# Main.net
KiCad netlist of a schematic drawn in Altium Designer
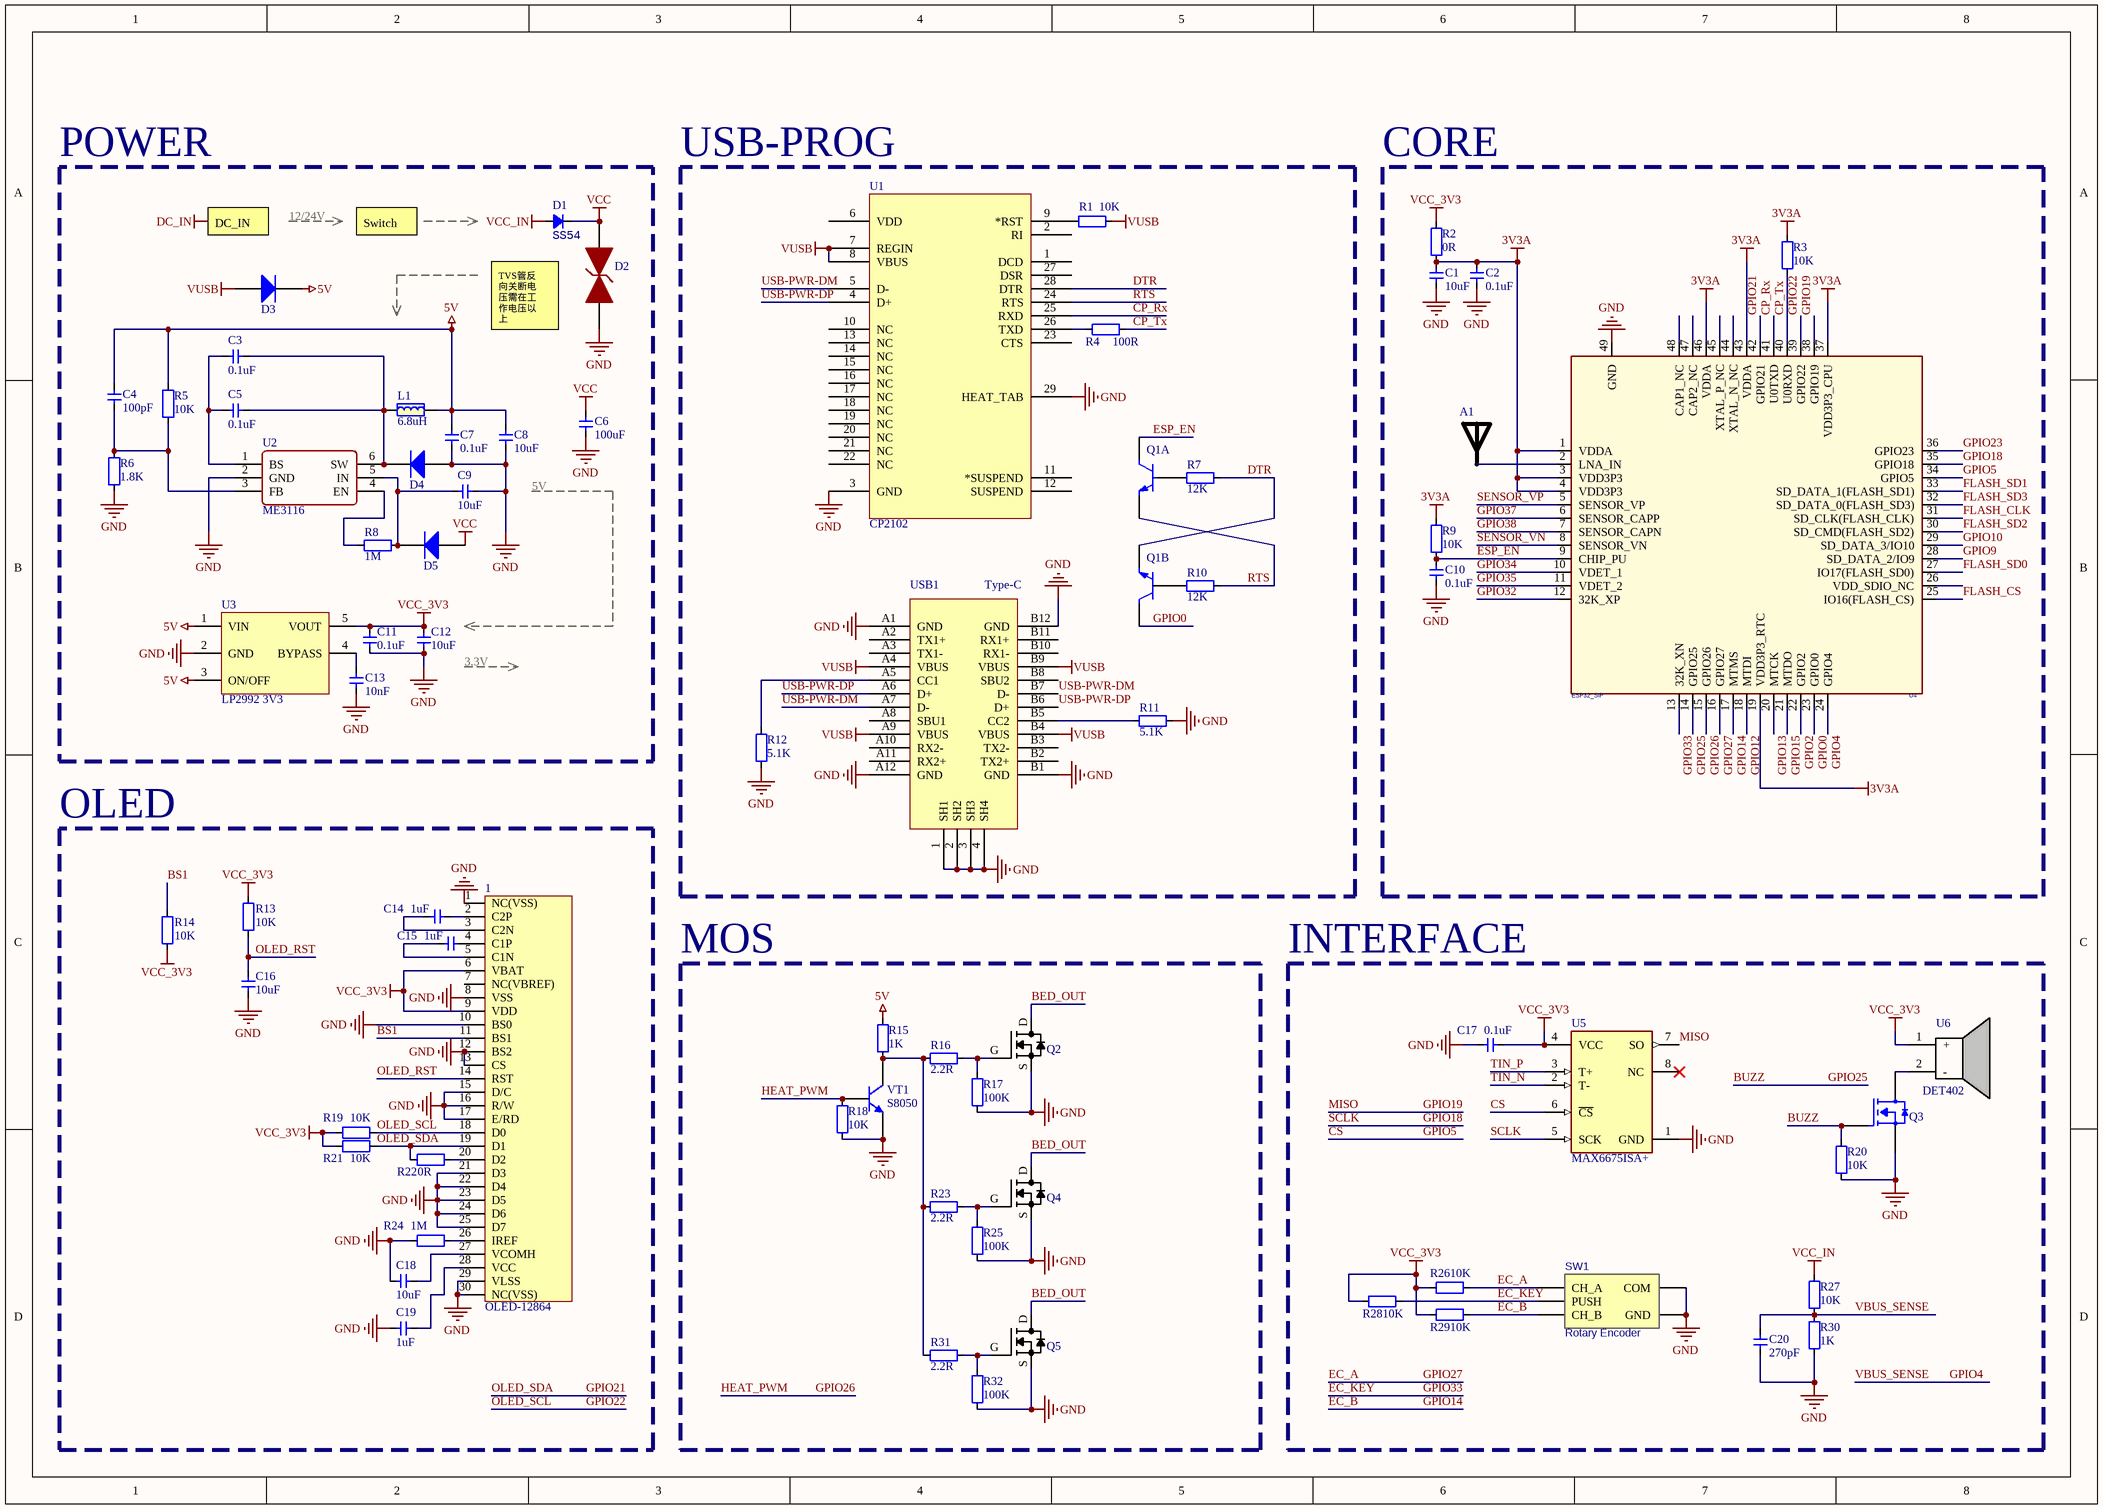
[diagram p0: Main.SchDoc]

(export (version "E")
  (design (tool "Eeschema 10.0.6"))
  (components
    (comp (ref "1")
      (value "OLED-12864")
      (footprint "OLED-12864-1.3-TOP")
      (description "显示屏")
      (libsource (lib "MyPcbLib") (part "OLED-12864"))
    )
    (comp (ref "A1")
      (value "RAINSUN")
      (footprint "ANT-Rainsun-AN5120")
      (libsource (lib "MyPcbLib") (part "ANT-Rainsun-AP5120"))
    )
    (comp (ref "C1")
      (value "10uF")
      (footprint "CAP_0402")
      (description "Capacitor")
      (libsource (lib "MyPcbLib") (part "电容-0402"))
    )
    (comp (ref "C2")
      (value "0.1uF")
      (footprint "CAP_0402")
      (description "Capacitor")
      (libsource (lib "MyPcbLib") (part "电容-0402"))
    )
    (comp (ref "C3")
      (value "0.1uF")
      (footprint "CAP_0402")
      (description "Capacitor")
      (libsource (lib "MyPcbLib") (part "电容-0402"))
    )
    (comp (ref "C4")
      (value "100pF")
      (footprint "CAP_0402")
      (description "Capacitor")
      (libsource (lib "MyPcbLib") (part "电容-0402"))
    )
    (comp (ref "C5")
      (value "0.1uF")
      (footprint "CAP_0402")
      (description "Capacitor")
      (libsource (lib "MyPcbLib") (part "电容-0402"))
    )
    (comp (ref "C6")
      (value "100uF")
      (footprint "1206-CAP")
      (description "Capacitor")
      (libsource (lib "MyPcbLib") (part "电容-1206"))
    )
    (comp (ref "C7")
      (value "0.1uF")
      (footprint "CAP_0402")
      (description "Capacitor")
      (libsource (lib "MyPcbLib") (part "电容-0402"))
    )
    (comp (ref "C8")
      (value "10uF")
      (footprint "CAP_0402")
      (description "Capacitor")
      (libsource (lib "MyPcbLib") (part "电容-0402"))
    )
    (comp (ref "C9")
      (value "10uF")
      (footprint "CAP_0402")
      (description "Capacitor")
      (libsource (lib "MyPcbLib") (part "电容-0402"))
    )
    (comp (ref "C10")
      (value "0.1uF")
      (footprint "CAP_0402")
      (description "Capacitor")
      (libsource (lib "MyPcbLib") (part "电容-0402"))
    )
    (comp (ref "C11")
      (value "0.1uF")
      (footprint "CAP_0402")
      (description "Capacitor")
      (libsource (lib "MyPcbLib") (part "电容-0402"))
    )
    (comp (ref "C12")
      (value "10uF")
      (footprint "CAP_0402")
      (description "Capacitor")
      (libsource (lib "MyPcbLib") (part "电容-0402"))
    )
    (comp (ref "C13")
      (value "10nF")
      (footprint "CAP_0402")
      (description "Capacitor")
      (libsource (lib "MyPcbLib") (part "电容-0402"))
    )
    (comp (ref "C14")
      (value "1uF")
      (footprint "CAP_0402")
      (description "Capacitor")
      (libsource (lib "MyPcbLib") (part "电容-0402"))
    )
    (comp (ref "C15")
      (value "1uF")
      (footprint "CAP_0402")
      (description "Capacitor")
      (libsource (lib "MyPcbLib") (part "电容-0402"))
    )
    (comp (ref "C16")
      (value "10uF")
      (footprint "CAP_0402")
      (description "Capacitor")
      (libsource (lib "MyPcbLib") (part "电容-0402"))
    )
    (comp (ref "C17")
      (value "0.1uF")
      (footprint "CAP_0402")
      (description "Capacitor")
      (libsource (lib "MyPcbLib") (part "电容-0402"))
    )
    (comp (ref "C18")
      (value "10uF")
      (footprint "CAP_0402")
      (description "Capacitor")
      (libsource (lib "MyPcbLib") (part "电容-0402"))
    )
    (comp (ref "C19")
      (value "1uF")
      (footprint "CAP_0402")
      (description "Capacitor")
      (libsource (lib "MyPcbLib") (part "电容-0402"))
    )
    (comp (ref "C20")
      (value "270pF")
      (footprint "CAP_0402")
      (description "Capacitor")
      (libsource (lib "MyPcbLib") (part "电容-0402"))
    )
    (comp (ref "D1")
      (value "SS54")
      (footprint "DO-214AC")
      (description "Diode")
      (libsource (lib "KitSprout") (part "Diode_SMA"))
    )
    (comp (ref "D2")
      (value "SMBJ28CA")
      (footprint "SMBJ-CA_MFG")
      (libsource (lib "MyPcbLib") (part "SMBJ28CA"))
    )
    (comp (ref "D3")
      (value "二极管-5819W")
      (footprint "SOD-323")
      (description "40V")
      (libsource (lib "MyPcbLib") (part "二极管-5819W"))
    )
    (comp (ref "D4")
      (value "二极管-5819W")
      (footprint "SOD-323")
      (description "40V")
      (libsource (lib "MyPcbLib") (part "二极管-5819W"))
    )
    (comp (ref "D5")
      (value "二极管-5819W")
      (footprint "SOD-323")
      (description "40V")
      (libsource (lib "MyPcbLib") (part "二极管-5819W"))
    )
    (comp (ref "L1") (value "6.8uH") (footprint "IND-201612") (libsource (lib "MyPcbLib") (part "电感-201612")))
    (comp (ref "Q1")
      (value "BC847BVC-7")
      (footprint "SOT563-6")
      (libsource (lib "MyPcbLib") (part "BC847BVC-7"))
    )
    (comp (ref "Q2")
      (value "NTMFS5C628NLT")
      (footprint "SO8FL")
      (description "MOSFET N-CH 60V SO8FL")
      (fields
        (field (name "MANUFACTURER") "ON Semiconductor")
        (field (name "MANUFACTURER PART NUMBER") "NTMFS5C628NLT1G")
      )
      (libsource (lib "MyPcbLib") (part "NTMFS5C628NLT"))
    )
    (comp (ref "Q3")
      (value "AO3400A")
      (footprint "SOT23-3")
      (description "N-MOS")
      (libsource (lib "MyPcbLib") (part "AO3400A"))
    )
    (comp (ref "Q4")
      (value "NTMFS5C628NLT")
      (footprint "SO8FL")
      (description "MOSFET N-CH 60V SO8FL")
      (fields
        (field (name "MANUFACTURER") "ON Semiconductor")
        (field (name "MANUFACTURER PART NUMBER") "NTMFS5C628NLT1G")
      )
      (libsource (lib "MyPcbLib") (part "NTMFS5C628NLT"))
    )
    (comp (ref "Q5")
      (value "NTMFS5C628NLT")
      (footprint "SO8FL")
      (description "MOSFET N-CH 60V SO8FL")
      (fields
        (field (name "MANUFACTURER") "ON Semiconductor")
        (field (name "MANUFACTURER PART NUMBER") "NTMFS5C628NLT1G")
      )
      (libsource (lib "MyPcbLib") (part "NTMFS5C628NLT"))
    )
    (comp (ref "R1")
      (value "10K")
      (footprint "RES_0402")
      (description "Resistor")
      (libsource (lib "") (part "电阻-0402_1"))
    )
    (comp (ref "R2")
      (value "0R")
      (footprint "RES_0402")
      (description "Resistor")
      (libsource (lib "") (part "电阻-0402_2"))
    )
    (comp (ref "R3")
      (value "10K")
      (footprint "RES_0402")
      (description "Resistor")
      (libsource (lib "") (part "电阻-0402_3"))
    )
    (comp (ref "R4")
      (value "100R")
      (footprint "RES_0402")
      (description "Resistor")
      (libsource (lib "") (part "电阻-0402_1"))
    )
    (comp (ref "R5")
      (value "10K")
      (footprint "RES_0402")
      (description "Resistor")
      (libsource (lib "") (part "电阻-0402_3"))
    )
    (comp (ref "R6")
      (value "1.8K")
      (footprint "RES_0402")
      (description "Resistor")
      (libsource (lib "") (part "电阻-0402_3"))
    )
    (comp (ref "R7")
      (value "12K")
      (footprint "RES_0402")
      (description "Resistor")
      (libsource (lib "") (part "电阻-0402_1"))
    )
    (comp (ref "R8")
      (value "1M")
      (footprint "RES_0402")
      (description "Resistor")
      (libsource (lib "") (part "电阻-0402_1"))
    )
    (comp (ref "R9")
      (value "10K")
      (footprint "RES_0402")
      (description "Resistor")
      (libsource (lib "") (part "电阻-0402_2"))
    )
    (comp (ref "R10")
      (value "12K")
      (footprint "RES_0402")
      (description "Resistor")
      (libsource (lib "") (part "电阻-0402_1"))
    )
    (comp (ref "R11")
      (value "5.1K")
      (footprint "RES_0402")
      (description "Resistor")
      (libsource (lib "") (part "电阻-0402_1"))
    )
    (comp (ref "R12")
      (value "5.1K")
      (footprint "RES_0402")
      (description "Resistor")
      (libsource (lib "") (part "电阻-0402_2"))
    )
    (comp (ref "R13")
      (value "10K")
      (footprint "RES_0402")
      (description "Resistor")
      (libsource (lib "") (part "电阻-0402_3"))
    )
    (comp (ref "R14")
      (value "10K")
      (footprint "RES_0402")
      (description "Resistor")
      (libsource (lib "") (part "电阻-0402_3"))
    )
    (comp (ref "R15")
      (value "1K")
      (footprint "RES_0402")
      (description "Resistor")
      (libsource (lib "") (part "电阻-0402_3"))
    )
    (comp (ref "R16")
      (value "2.2R")
      (footprint "RES_0402")
      (description "Resistor")
      (libsource (lib "") (part "电阻-0402_1"))
    )
    (comp (ref "R17")
      (value "100K")
      (footprint "RES_0402")
      (description "Resistor")
      (libsource (lib "") (part "电阻-0402_2"))
    )
    (comp (ref "R18")
      (value "10K")
      (footprint "RES_0402")
      (description "Resistor")
      (libsource (lib "") (part "电阻-0402_2"))
    )
    (comp (ref "R19")
      (value "10K")
      (footprint "RES_0402")
      (description "Resistor")
      (libsource (lib "MyPcbLib") (part "电阻-0402"))
    )
    (comp (ref "R20")
      (value "10K")
      (footprint "RES_0402")
      (description "Resistor")
      (libsource (lib "") (part "电阻-0402_3"))
    )
    (comp (ref "R21")
      (value "10K")
      (footprint "RES_0402")
      (description "Resistor")
      (libsource (lib "MyPcbLib") (part "电阻-0402"))
    )
    (comp (ref "R22")
      (value "0R")
      (footprint "RES_0402")
      (description "Resistor")
      (libsource (lib "") (part "电阻-0402_1"))
    )
    (comp (ref "R23")
      (value "2.2R")
      (footprint "RES_0402")
      (description "Resistor")
      (libsource (lib "") (part "电阻-0402_1"))
    )
    (comp (ref "R24")
      (value "1M")
      (footprint "RES_0402")
      (description "Resistor")
      (libsource (lib "MyPcbLib") (part "电阻-0402"))
    )
    (comp (ref "R25")
      (value "100K")
      (footprint "RES_0402")
      (description "Resistor")
      (libsource (lib "") (part "电阻-0402_2"))
    )
    (comp (ref "R26")
      (value "10K")
      (footprint "RES_0402")
      (description "Resistor")
      (libsource (lib "") (part "电阻-0402_1"))
    )
    (comp (ref "R27")
      (value "10K")
      (footprint "RES_0402")
      (description "Resistor")
      (libsource (lib "") (part "电阻-0402_2"))
    )
    (comp (ref "R28")
      (value "10K")
      (footprint "RES_0402")
      (description "Resistor")
      (libsource (lib "") (part "电阻-0402_1"))
    )
    (comp (ref "R29")
      (value "10K")
      (footprint "RES_0402")
      (description "Resistor")
      (libsource (lib "") (part "电阻-0402_1"))
    )
    (comp (ref "R30")
      (value "1K")
      (footprint "RES_0402")
      (description "Resistor")
      (libsource (lib "") (part "电阻-0402_2"))
    )
    (comp (ref "R31")
      (value "2.2R")
      (footprint "RES_0402")
      (description "Resistor")
      (libsource (lib "") (part "电阻-0402_1"))
    )
    (comp (ref "R32")
      (value "100K")
      (footprint "RES_0402")
      (description "Resistor")
      (libsource (lib "") (part "电阻-0402_2"))
    )
    (comp (ref "SW1")
      (value "Rotary Encoder")
      (footprint "SIQ-02FVS3")
      (fields
        (field (name "BOM_SUPPLIER PART") "C1322543")
        (field (name "BOM_MANUFACTURER PART") "EC11E1534443")
        (field (name "CONTRIBUTOR") "LCSC")
      )
      (libsource (lib "MyPcbLib") (part "Rotary Encoder"))
    )
    (comp (ref "U1")
      (value "CP2102")
      (footprint "QFN-28")
      (description "USB转TTL")
      (libsource (lib "mLib") (part "CP2102"))
    )
    (comp (ref "U2")
      (value "ME3116")
      (footprint "SOT23-6")
      (description "DC-DC")
      (libsource (lib "MyPcbLib") (part "ME3116"))
    )
    (comp (ref "U3")
      (value "LP2992 3V3")
      (footprint "SOT23-5")
      (description "LDO")
      (libsource (lib "mLib") (part "LP2992"))
    )
    (comp (ref "U4")
      (value "ESP32_SIP")
      (footprint "QFN-48_7X7")
      (libsource (lib "mLib") (part "ESP32-PICO"))
    )
    (comp (ref "U5")
      (value "MAX6675ISA")
      (footprint "SO-8")
      (description "IC THERMOCOUP TO DGTL 8-SOIC")
      (fields
        (field (name "MANUFACTURER") "Maxim Electronics")
        (field (name "OCTOPART PART NUMBER") "33bcfab92ad8ec7b")
        (field (name "PART NUMBER") "MAX6675ISA+")
      )
      (libsource (lib "MyPcbLib") (part "MAX6675ISA"))
    )
    (comp (ref "U6") (value "DET402") (footprint "DET402") (libsource (lib "MyPcbLib") (part "DET402")))
    (comp (ref "USB1")
      (value "Type-C")
      (footprint "Type-C-TOP")
      (libsource (lib "MyPcbLib") (part "USB-Type-C-TOP"))
    )
    (comp (ref "VT1")
      (value "S8050")
      (footprint "SMT_TRIODE_NPN")
      (description "Surface mount NPN transistor, package SOT-23")
      (libsource (lib "MyPcbLib") (part "SMT_TRIODE_NPN"))
    )
  )
  (nets
    (net (code "1") (name "/BED_OUT") (class "Default")
      (node (ref "Q2") (pin "D") (pinfunction "D_D") (pintype "passive"))
      (node (ref "Q4") (pin "D") (pinfunction "D_D") (pintype "passive"))
      (node (ref "Q5") (pin "D") (pinfunction "D_D") (pintype "passive"))
    )
    (net (code "2") (name "/BS1") (class "Default")
      (node (ref "1") (pin "11") (pinfunction "BS1_11") (pintype "passive"))
      (node (ref "R14") (pin "2") (pinfunction "2_2") (pintype "passive"))
    )
    (net (code "3") (name "/BUZZ") (class "Default")
      (node (ref "Q3") (pin "1") (pinfunction "G_1") (pintype "passive"))
      (node (ref "R20") (pin "2") (pinfunction "2_2") (pintype "passive"))
      (node (ref "U4") (pin "14") (pinfunction "GPIO25_14") (pintype "passive"))
    )
    (net (code "4") (name "/CP_Rx") (class "Default")
      (node (ref "U1") (pin "25") (pinfunction "RXD_25") (pintype "passive"))
      (node (ref "U4") (pin "41") (pinfunction "U0TXD_41") (pintype "power_in"))
    )
    (net (code "5") (name "/CP_Tx") (class "Default")
      (node (ref "R3") (pin "1") (pinfunction "1_1") (pintype "passive"))
      (node (ref "R4") (pin "1") (pinfunction "1_1") (pintype "passive"))
      (node (ref "U4") (pin "40") (pinfunction "U0RXD_40") (pintype "power_in"))
    )
    (net (code "6") (name "/CS") (class "Default")
      (node (ref "U4") (pin "34") (pinfunction "GPIO5_34") (pintype "passive"))
      (node (ref "U5") (pin "6") (pinfunction "~{CS}_6") (pintype "input"))
    )
    (net (code "7") (name "/DTR") (class "Default")
      (node (ref "Q1") (pin "4") (pinfunction "E2_4") (pintype "passive"))
      (node (ref "R7") (pin "1") (pinfunction "1_1") (pintype "passive"))
      (node (ref "U1") (pin "28") (pinfunction "DTR_28") (pintype "passive"))
    )
    (net (code "8") (name "/EC_A") (class "Default")
      (node (ref "R26") (pin "1") (pinfunction "1_1") (pintype "passive"))
      (node (ref "SW1") (pin "1") (pinfunction "CH_A_1") (pintype "passive"))
      (node (ref "U4") (pin "16") (pinfunction "GPIO27_16") (pintype "passive"))
    )
    (net (code "9") (name "/EC_B") (class "Default")
      (node (ref "R29") (pin "1") (pinfunction "1_1") (pintype "passive"))
      (node (ref "SW1") (pin "4") (pinfunction "CH_B_4") (pintype "passive"))
      (node (ref "U4") (pin "17") (pinfunction "MTMS_17") (pintype "passive"))
    )
    (net (code "10") (name "/EC_KEY") (class "Default")
      (node (ref "R28") (pin "1") (pinfunction "1_1") (pintype "passive"))
      (node (ref "SW1") (pin "2") (pinfunction "PUSH_2") (pintype "passive"))
      (node (ref "U4") (pin "13") (pinfunction "32K_XN_13") (pintype "passive"))
    )
    (net (code "11") (name "/ESP_EN") (class "Default")
      (node (ref "C10") (pin "1") (pinfunction "1_1") (pintype "passive"))
      (node (ref "Q1") (pin "6") (pinfunction "C1_6") (pintype "passive"))
      (node (ref "R9") (pin "2") (pinfunction "2_2") (pintype "passive"))
      (node (ref "U4") (pin "9") (pinfunction "CHIP_PU_9") (pintype "passive"))
    )
    (net (code "12") (name "/FLASH_CLK") (class "Default")
      (node (ref "U4") (pin "31") (pinfunction "SD_CLK(FLASH_CLK)_31") (pintype "passive"))
    )
    (net (code "13") (name "/FLASH_CS") (class "Default")
      (node (ref "U4") (pin "25") (pinfunction "IO16(FLASH_CS)_25") (pintype "passive"))
    )
    (net (code "14") (name "/FLASH_SD0") (class "Default")
      (node (ref "U4") (pin "27") (pinfunction "IO17(FLASH_SD0)_27") (pintype "passive"))
    )
    (net (code "15") (name "/FLASH_SD1") (class "Default")
      (node (ref "U4") (pin "33") (pinfunction "SD_DATA_1(FLASH_SD1)_33") (pintype "passive"))
    )
    (net (code "16") (name "/FLASH_SD2") (class "Default")
      (node (ref "U4") (pin "30") (pinfunction "SD_CMD(FLASH_SD2)_30") (pintype "passive"))
    )
    (net (code "17") (name "/FLASH_SD3") (class "Default")
      (node (ref "U4") (pin "32") (pinfunction "SD_DATA_0(FLASH_SD3)_32") (pintype "passive"))
    )
    (net (code "18") (name "/GPIO0") (class "Default")
      (node (ref "Q1") (pin "3") (pinfunction "C2_3") (pintype "passive"))
      (node (ref "U4") (pin "23") (pinfunction "GPIO0_23") (pintype "passive"))
    )
    (net (code "19") (name "/GPIO2") (class "Default")
      (node (ref "U4") (pin "22") (pinfunction "GPIO2_22") (pintype "passive"))
    )
    (net (code "20") (name "/GPIO4") (class "Default")
      (node (ref "C20") (pin "2") (pinfunction "2_2") (pintype "passive"))
      (node (ref "R27") (pin "2") (pinfunction "2_2") (pintype "passive"))
      (node (ref "R30") (pin "1") (pinfunction "1_1") (pintype "passive"))
      (node (ref "U4") (pin "24") (pinfunction "GPIO4_24") (pintype "passive"))
    )
    (net (code "21") (name "/GPIO9") (class "Default")
      (node (ref "U4") (pin "28") (pinfunction "SD_DATA_2/IO9_28") (pintype "passive"))
    )
    (net (code "22") (name "/GPIO10") (class "Default")
      (node (ref "U4") (pin "29") (pinfunction "SD_DATA_3/IO10_29") (pintype "passive"))
    )
    (net (code "23") (name "/GPIO12") (class "Default")
      (node (ref "U4") (pin "18") (pinfunction "MTDI_18") (pintype "passive"))
    )
    (net (code "24") (name "/GPIO13") (class "Default")
      (node (ref "U4") (pin "20") (pinfunction "MTCK_20") (pintype "passive"))
    )
    (net (code "25") (name "/GPIO15") (class "Default")
      (node (ref "U4") (pin "21") (pinfunction "MTDO_21") (pintype "passive"))
    )
    (net (code "26") (name "/GPIO18") (class "Default")
      (node (ref "U4") (pin "35") (pinfunction "GPIO18_35") (pintype "passive"))
      (node (ref "U5") (pin "5") (pinfunction "SCK_5") (pintype "input"))
    )
    (net (code "27") (name "/GPIO19") (class "Default")
      (node (ref "U4") (pin "38") (pinfunction "GPIO19_38") (pintype "passive"))
      (node (ref "U5") (pin "7") (pinfunction "SO_7") (pintype "output"))
    )
    (net (code "28") (name "/GPIO21") (class "Default")
      (node (ref "1") (pin "19") (pinfunction "D1_19") (pintype "passive"))
      (node (ref "R21") (pin "2") (pinfunction "2_2") (pintype "passive"))
      (node (ref "R22") (pin "2") (pinfunction "2_2") (pintype "passive"))
      (node (ref "U4") (pin "42") (pinfunction "GPIO21_42") (pintype "passive"))
    )
    (net (code "29") (name "/GPIO22") (class "Default")
      (node (ref "1") (pin "18") (pinfunction "D0_18") (pintype "passive"))
      (node (ref "R19") (pin "2") (pinfunction "2_2") (pintype "passive"))
      (node (ref "U4") (pin "39") (pinfunction "GPIO22_39") (pintype "passive"))
    )
    (net (code "30") (name "/GPIO23") (class "Default")
      (node (ref "U4") (pin "36") (pinfunction "GPIO23_36") (pintype "passive"))
    )
    (net (code "31") (name "/GPIO26") (class "Default")
      (node (ref "R18") (pin "1") (pinfunction "1_1") (pintype "passive"))
      (node (ref "U4") (pin "15") (pinfunction "GPIO26_15") (pintype "passive"))
      (node (ref "VT1") (pin "1") (pinfunction "B_1") (pintype "passive"))
    )
    (net (code "32") (name "/GPIO32") (class "Default")
      (node (ref "U4") (pin "12") (pinfunction "32K_XP_12") (pintype "passive"))
    )
    (net (code "33") (name "/GPIO34") (class "Default")
      (node (ref "U4") (pin "10") (pinfunction "VDET_1_10") (pintype "passive"))
    )
    (net (code "34") (name "/GPIO35") (class "Default")
      (node (ref "U4") (pin "11") (pinfunction "VDET_2_11") (pintype "passive"))
    )
    (net (code "35") (name "/GPIO37") (class "Default")
      (node (ref "U4") (pin "6") (pinfunction "SENSOR_CAPP_6") (pintype "passive"))
    )
    (net (code "36") (name "/GPIO38") (class "Default")
      (node (ref "U4") (pin "7") (pinfunction "SENSOR_CAPN_7") (pintype "passive"))
    )
    (net (code "37") (name "/OLED_RST") (class "Default")
      (node (ref "1") (pin "14") (pinfunction "RST_14") (pintype "passive"))
      (node (ref "C16") (pin "2") (pinfunction "2_2") (pintype "passive"))
      (node (ref "R13") (pin "1") (pinfunction "1_1") (pintype "passive"))
    )
    (net (code "38") (name "/RTS") (class "Default")
      (node (ref "Q1") (pin "1") (pinfunction "E1_1") (pintype "passive"))
      (node (ref "R10") (pin "1") (pinfunction "1_1") (pintype "passive"))
      (node (ref "U1") (pin "24") (pinfunction "RTS_24") (pintype "passive"))
    )
    (net (code "39") (name "/SENSOR_VN") (class "Default")
      (node (ref "U4") (pin "8") (pinfunction "SENSOR_VN_8") (pintype "passive"))
    )
    (net (code "40") (name "/SENSOR_VP") (class "Default")
      (node (ref "U4") (pin "5") (pinfunction "SENSOR_VP_5") (pintype "passive"))
    )
    (net (code "41") (name "/TIN_N") (class "Default")
      (node (ref "U5") (pin "2") (pinfunction "T-_2") (pintype "input"))
    )
    (net (code "42") (name "/TIN_P") (class "Default")
      (node (ref "U5") (pin "3") (pinfunction "T+_3") (pintype "input"))
    )
    (net (code "43") (name "/USB-PWR-DM") (class "Default")
      (node (ref "U1") (pin "5") (pinfunction "D-_5") (pintype "passive"))
      (node (ref "USB1") (pin "A7") (pinfunction "D-_A7") (pintype "passive"))
      (node (ref "USB1") (pin "B7") (pinfunction "D-_B7") (pintype "passive"))
    )
    (net (code "44") (name "/USB-PWR-DP") (class "Default")
      (node (ref "U1") (pin "4") (pinfunction "D+_4") (pintype "passive"))
      (node (ref "USB1") (pin "A6") (pinfunction "D+_A6") (pintype "passive"))
      (node (ref "USB1") (pin "B6") (pinfunction "D+_B6") (pintype "passive"))
    )
    (net (code "45") (name "3V3A") (class "Default")
      (node (ref "C1") (pin "2") (pinfunction "2_2") (pintype "passive"))
      (node (ref "C2") (pin "2") (pinfunction "2_2") (pintype "passive"))
      (node (ref "R2") (pin "2") (pinfunction "2_2") (pintype "passive"))
      (node (ref "R3") (pin "2") (pinfunction "2_2") (pintype "passive"))
      (node (ref "R9") (pin "1") (pinfunction "1_1") (pintype "passive"))
      (node (ref "U4") (pin "1") (pinfunction "VDDA_1") (pintype "power_in"))
      (node (ref "U4") (pin "19") (pinfunction "VDD3P3_RTC_19") (pintype "power_in"))
      (node (ref "U4") (pin "3") (pinfunction "VDD3P3_3") (pintype "power_in"))
      (node (ref "U4") (pin "37") (pinfunction "VDD3P3_CPU_37") (pintype "power_in"))
      (node (ref "U4") (pin "4") (pinfunction "VDD3P3_4") (pintype "power_in"))
      (node (ref "U4") (pin "43") (pinfunction "VDDA_43") (pintype "power_in"))
      (node (ref "U4") (pin "46") (pinfunction "VDDA_46") (pintype "power_in"))
    )
    (net (code "46") (name "5V") (class "Default")
      (node (ref "C4") (pin "1") (pinfunction "1_1") (pintype "passive"))
      (node (ref "C7") (pin "2") (pinfunction "2_2") (pintype "passive"))
      (node (ref "C8") (pin "2") (pinfunction "2_2") (pintype "passive"))
      (node (ref "D3") (pin "2") (pinfunction "K_2") (pintype "passive"))
      (node (ref "L1") (pin "2") (pinfunction "2_2") (pintype "passive"))
      (node (ref "R15") (pin "2") (pinfunction "2_2") (pintype "passive"))
      (node (ref "R5") (pin "2") (pinfunction "2_2") (pintype "passive"))
      (node (ref "U3") (pin "1") (pinfunction "VIN_1") (pintype "passive"))
      (node (ref "U3") (pin "3") (pinfunction "ON/OFF_3") (pintype "passive"))
    )
    (net (code "48") (name "GND") (class "Default")
      (node (ref "1") (pin "1") (pinfunction "NC(VSS)_1") (pintype "passive"))
      (node (ref "1") (pin "10") (pinfunction "BS0_10") (pintype "passive"))
      (node (ref "1") (pin "12") (pinfunction "BS2_12") (pintype "passive"))
      (node (ref "1") (pin "13") (pinfunction "CS_13") (pintype "passive"))
      (node (ref "1") (pin "15") (pinfunction "D/C_15") (pintype "passive"))
      (node (ref "1") (pin "16") (pinfunction "R/W_16") (pintype "passive"))
      (node (ref "1") (pin "17") (pinfunction "E/RD_17") (pintype "passive"))
      (node (ref "1") (pin "21") (pinfunction "D3_21") (pintype "passive"))
      (node (ref "1") (pin "22") (pinfunction "D4_22") (pintype "passive"))
      (node (ref "1") (pin "23") (pinfunction "D5_23") (pintype "passive"))
      (node (ref "1") (pin "24") (pinfunction "D6_24") (pintype "passive"))
      (node (ref "1") (pin "25") (pinfunction "D7_25") (pintype "passive"))
      (node (ref "1") (pin "29") (pinfunction "VLSS_29") (pintype "passive"))
      (node (ref "1") (pin "30") (pinfunction "NC(VSS)_30") (pintype "passive"))
      (node (ref "1") (pin "8") (pinfunction "VSS_8") (pintype "passive"))
      (node (ref "C1") (pin "1") (pinfunction "1_1") (pintype "passive"))
      (node (ref "C10") (pin "2") (pinfunction "2_2") (pintype "passive"))
      (node (ref "C11") (pin "1") (pinfunction "1_1") (pintype "passive"))
      (node (ref "C12") (pin "1") (pinfunction "1_1") (pintype "passive"))
      (node (ref "C13") (pin "1") (pinfunction "1_1") (pintype "passive"))
      (node (ref "C16") (pin "1") (pinfunction "1_1") (pintype "passive"))
      (node (ref "C17") (pin "2") (pinfunction "2_2") (pintype "passive"))
      (node (ref "C18") (pin "2") (pinfunction "2_2") (pintype "passive"))
      (node (ref "C19") (pin "2") (pinfunction "2_2") (pintype "passive"))
      (node (ref "C2") (pin "1") (pinfunction "1_1") (pintype "passive"))
      (node (ref "C20") (pin "1") (pinfunction "1_1") (pintype "passive"))
      (node (ref "C6") (pin "1") (pinfunction "1_1") (pintype "passive"))
      (node (ref "C7") (pin "1") (pinfunction "1_1") (pintype "passive"))
      (node (ref "C8") (pin "1") (pinfunction "1_1") (pintype "passive"))
      (node (ref "C9") (pin "1") (pinfunction "1_1") (pintype "passive"))
      (node (ref "D2") (pin "1") (pinfunction "1_1") (pintype "passive"))
      (node (ref "D4") (pin "1") (pinfunction "A_1") (pintype "passive"))
      (node (ref "Q2") (pin "S") (pinfunction "S_S") (pintype "passive"))
      (node (ref "Q3") (pin "2") (pinfunction "S_2") (pintype "passive"))
      (node (ref "Q4") (pin "S") (pinfunction "S_S") (pintype "passive"))
      (node (ref "Q5") (pin "S") (pinfunction "S_S") (pintype "passive"))
      (node (ref "R11") (pin "1") (pinfunction "1_1") (pintype "passive"))
      (node (ref "R12") (pin "2") (pinfunction "2_2") (pintype "passive"))
      (node (ref "R17") (pin "2") (pinfunction "2_2") (pintype "passive"))
      (node (ref "R18") (pin "2") (pinfunction "2_2") (pintype "passive"))
      (node (ref "R20") (pin "1") (pinfunction "1_1") (pintype "passive"))
      (node (ref "R24") (pin "1") (pinfunction "1_1") (pintype "passive"))
      (node (ref "R25") (pin "2") (pinfunction "2_2") (pintype "passive"))
      (node (ref "R30") (pin "2") (pinfunction "2_2") (pintype "passive"))
      (node (ref "R32") (pin "2") (pinfunction "2_2") (pintype "passive"))
      (node (ref "R6") (pin "1") (pinfunction "1_1") (pintype "passive"))
      (node (ref "SW1") (pin "3") (pinfunction "COM_3") (pintype "passive"))
      (node (ref "SW1") (pin "5") (pinfunction "GND_5") (pintype "passive"))
      (node (ref "U1") (pin "29") (pinfunction "HEAT_TAB_29") (pintype "passive"))
      (node (ref "U1") (pin "3") (pinfunction "GND_3") (pintype "passive"))
      (node (ref "U2") (pin "2") (pinfunction "GND_2") (pintype "passive"))
      (node (ref "U3") (pin "2") (pinfunction "GND_2") (pintype "passive"))
      (node (ref "U4") (pin "49") (pinfunction "GND_49") (pintype "power_in"))
      (node (ref "U5") (pin "1") (pinfunction "GND_1") (pintype "power_in"))
      (node (ref "USB1") (pin "1") (pinfunction "SH1_1") (pintype "passive"))
      (node (ref "USB1") (pin "2") (pinfunction "SH2_2") (pintype "passive"))
      (node (ref "USB1") (pin "3") (pinfunction "SH3_3") (pintype "passive"))
      (node (ref "USB1") (pin "4") (pinfunction "SH4_4") (pintype "passive"))
      (node (ref "USB1") (pin "A1") (pinfunction "GND_A1") (pintype "passive"))
      (node (ref "USB1") (pin "A12") (pinfunction "GND_A12") (pintype "passive"))
      (node (ref "USB1") (pin "B1") (pinfunction "GND_B1") (pintype "passive"))
      (node (ref "USB1") (pin "B12") (pinfunction "GND_B12") (pintype "passive"))
      (node (ref "VT1") (pin "2") (pinfunction "E_2") (pintype "passive"))
    )
    (net (code "49") (name "Net-(1-C1N)") (class "Default")
      (node (ref "1") (pin "5") (pinfunction "C1N_5") (pintype "passive"))
      (node (ref "C15") (pin "2") (pinfunction "2_2") (pintype "passive"))
    )
    (net (code "50") (name "Net-(1-C1P)") (class "Default")
      (node (ref "1") (pin "4") (pinfunction "C1P_4") (pintype "passive"))
      (node (ref "C15") (pin "1") (pinfunction "1_1") (pintype "passive"))
    )
    (net (code "51") (name "Net-(1-C2N)") (class "Default")
      (node (ref "1") (pin "3") (pinfunction "C2N_3") (pintype "passive"))
      (node (ref "C14") (pin "2") (pinfunction "2_2") (pintype "passive"))
    )
    (net (code "52") (name "Net-(1-C2P)") (class "Default")
      (node (ref "1") (pin "2") (pinfunction "C2P_2") (pintype "passive"))
      (node (ref "C14") (pin "1") (pinfunction "1_1") (pintype "passive"))
    )
    (net (code "53") (name "Net-(1-D2)") (class "Default")
      (node (ref "1") (pin "20") (pinfunction "D2_20") (pintype "passive"))
      (node (ref "R22") (pin "1") (pinfunction "1_1") (pintype "passive"))
    )
    (net (code "54") (name "Net-(1-IREF)") (class "Default")
      (node (ref "1") (pin "26") (pinfunction "IREF_26") (pintype "passive"))
      (node (ref "R24") (pin "2") (pinfunction "2_2") (pintype "passive"))
    )
    (net (code "55") (name "Net-(1-VCC)") (class "Default")
      (node (ref "1") (pin "28") (pinfunction "VCC_28") (pintype "passive"))
      (node (ref "C19") (pin "1") (pinfunction "1_1") (pintype "passive"))
    )
    (net (code "56") (name "Net-(1-VCOMH)") (class "Default")
      (node (ref "1") (pin "27") (pinfunction "VCOMH_27") (pintype "passive"))
      (node (ref "C18") (pin "1") (pinfunction "1_1") (pintype "passive"))
    )
    (net (code "57") (name "Net-(D4-K)") (class "Default")
      (node (ref "C3") (pin "1") (pinfunction "1_1") (pintype "passive"))
      (node (ref "C5") (pin "1") (pinfunction "1_1") (pintype "passive"))
      (node (ref "D4") (pin "2") (pinfunction "K_2") (pintype "passive"))
      (node (ref "L1") (pin "1") (pintype "passive"))
      (node (ref "U2") (pin "6") (pinfunction "SW_6") (pintype "passive"))
    )
    (net (code "58") (name "Net-(D5-K)") (class "Default")
      (node (ref "C9") (pin "2") (pinfunction "2_2") (pintype "passive"))
      (node (ref "D5") (pin "2") (pinfunction "K_2") (pintype "passive"))
      (node (ref "R8") (pin "1") (pinfunction "1_1") (pintype "passive"))
      (node (ref "U2") (pin "5") (pinfunction "IN_5") (pintype "passive"))
    )
    (net (code "59") (name "Net-(Q1A-B1)") (class "Default")
      (node (ref "Q1") (pin "2") (pinfunction "B1_2") (pintype "passive"))
      (node (ref "R7") (pin "2") (pinfunction "2_2") (pintype "passive"))
    )
    (net (code "60") (name "Net-(Q1B-B2)") (class "Default")
      (node (ref "Q1") (pin "5") (pinfunction "B2_5") (pintype "passive"))
      (node (ref "R10") (pin "2") (pinfunction "2_2") (pintype "passive"))
    )
    (net (code "61") (name "Net-(Q2-PadG)") (class "Default")
      (node (ref "Q2") (pin "G") (pinfunction "G_G") (pintype "passive"))
      (node (ref "R16") (pin "1") (pinfunction "1_1") (pintype "passive"))
      (node (ref "R17") (pin "1") (pinfunction "1_1") (pintype "passive"))
    )
    (net (code "62") (name "Net-(Q3-D)") (class "Default")
      (node (ref "Q3") (pin "3") (pinfunction "D_3") (pintype "passive"))
      (node (ref "U6") (pin "2") (pinfunction "-_2") (pintype "passive"))
    )
    (net (code "63") (name "Net-(Q4-PadG)") (class "Default")
      (node (ref "Q4") (pin "G") (pinfunction "G_G") (pintype "passive"))
      (node (ref "R23") (pin "1") (pinfunction "1_1") (pintype "passive"))
      (node (ref "R25") (pin "1") (pinfunction "1_1") (pintype "passive"))
    )
    (net (code "64") (name "Net-(Q5-PadG)") (class "Default")
      (node (ref "Q5") (pin "G") (pinfunction "G_G") (pintype "passive"))
      (node (ref "R31") (pin "1") (pinfunction "1_1") (pintype "passive"))
      (node (ref "R32") (pin "1") (pinfunction "1_1") (pintype "passive"))
    )
    (net (code "65") (name "Net-(U1-*RST)") (class "Default")
      (node (ref "R1") (pin "2") (pinfunction "2_2") (pintype "passive"))
      (node (ref "U1") (pin "9") (pinfunction "*RST_9") (pintype "passive"))
    )
    (net (code "66") (name "Net-(U1-TXD)") (class "Default")
      (node (ref "R4") (pin "2") (pinfunction "2_2") (pintype "passive"))
      (node (ref "U1") (pin "26") (pinfunction "TXD_26") (pintype "passive"))
    )
    (net (code "67") (name "Net-(U2-BS)") (class "Default")
      (node (ref "C3") (pin "2") (pinfunction "2_2") (pintype "passive"))
      (node (ref "C5") (pin "2") (pinfunction "2_2") (pintype "passive"))
      (node (ref "U2") (pin "1") (pinfunction "BS_1") (pintype "passive"))
    )
    (net (code "68") (name "Net-(U2-EN)") (class "Default")
      (node (ref "R8") (pin "2") (pinfunction "2_2") (pintype "passive"))
      (node (ref "U2") (pin "4") (pinfunction "EN_4") (pintype "passive"))
    )
    (net (code "69") (name "Net-(U2-FB)") (class "Default")
      (node (ref "C4") (pin "2") (pinfunction "2_2") (pintype "passive"))
      (node (ref "R5") (pin "1") (pinfunction "1_1") (pintype "passive"))
      (node (ref "R6") (pin "2") (pinfunction "2_2") (pintype "passive"))
      (node (ref "U2") (pin "3") (pinfunction "FB_3") (pintype "passive"))
    )
    (net (code "70") (name "Net-(U3-BYPASS)") (class "Default")
      (node (ref "C13") (pin "2") (pinfunction "2_2") (pintype "passive"))
      (node (ref "U3") (pin "4") (pinfunction "BYPASS_4") (pintype "passive"))
    )
    (net (code "71") (name "Net-(U4-LNA_IN)") (class "Default")
      (node (ref "A1") (pin "1") (pinfunction "1_1") (pintype "passive"))
      (node (ref "U4") (pin "2") (pinfunction "LNA_IN_2") (pintype "passive"))
    )
    (net (code "72") (name "Net-(USB1-CC1)") (class "Default")
      (node (ref "R12") (pin "1") (pinfunction "1_1") (pintype "passive"))
      (node (ref "USB1") (pin "A5") (pinfunction "CC1_A5") (pintype "passive"))
    )
    (net (code "73") (name "Net-(USB1-CC2)") (class "Default")
      (node (ref "R11") (pin "2") (pinfunction "2_2") (pintype "passive"))
      (node (ref "USB1") (pin "B5") (pinfunction "CC2_B5") (pintype "passive"))
    )
    (net (code "74") (name "Net-(VT1-C)") (class "Default")
      (node (ref "R15") (pin "1") (pinfunction "1_1") (pintype "passive"))
      (node (ref "R16") (pin "2") (pinfunction "2_2") (pintype "passive"))
      (node (ref "R23") (pin "2") (pinfunction "2_2") (pintype "passive"))
      (node (ref "R31") (pin "2") (pinfunction "2_2") (pintype "passive"))
      (node (ref "VT1") (pin "3") (pinfunction "C_3") (pintype "passive"))
    )
    (net (code "75") (name "VCC") (class "Default")
      (node (ref "C6") (pin "2") (pinfunction "2_2") (pintype "passive"))
      (node (ref "D1") (pin "2") (pinfunction "K_2") (pintype "passive"))
      (node (ref "D2") (pin "2") (pinfunction "2_2") (pintype "passive"))
      (node (ref "D5") (pin "1") (pinfunction "A_1") (pintype "passive"))
    )
    (net (code "76") (name "VCC_3V3") (class "Default")
      (node (ref "1") (pin "6") (pinfunction "VBAT_6") (pintype "passive"))
      (node (ref "1") (pin "9") (pinfunction "VDD_9") (pintype "passive"))
      (node (ref "C11") (pin "2") (pinfunction "2_2") (pintype "passive"))
      (node (ref "C12") (pin "2") (pinfunction "2_2") (pintype "passive"))
      (node (ref "C17") (pin "1") (pinfunction "1_1") (pintype "passive"))
      (node (ref "R13") (pin "2") (pinfunction "2_2") (pintype "passive"))
      (node (ref "R14") (pin "1") (pinfunction "1_1") (pintype "passive"))
      (node (ref "R19") (pin "1") (pinfunction "1_1") (pintype "passive"))
      (node (ref "R2") (pin "1") (pinfunction "1_1") (pintype "passive"))
      (node (ref "R21") (pin "1") (pinfunction "1_1") (pintype "passive"))
      (node (ref "R26") (pin "2") (pinfunction "2_2") (pintype "passive"))
      (node (ref "R28") (pin "2") (pinfunction "2_2") (pintype "passive"))
      (node (ref "R29") (pin "2") (pinfunction "2_2") (pintype "passive"))
      (node (ref "U3") (pin "5") (pinfunction "VOUT_5") (pintype "passive"))
      (node (ref "U5") (pin "4") (pinfunction "VCC_4") (pintype "power_in"))
      (node (ref "U6") (pin "1") (pinfunction "+_1") (pintype "passive"))
    )
    (net (code "77") (name "VCC_IN") (class "Default")
      (node (ref "D1") (pin "1") (pinfunction "A_1") (pintype "passive"))
      (node (ref "R27") (pin "1") (pinfunction "1_1") (pintype "passive"))
    )
    (net (code "78") (name "VUSB") (class "Default")
      (node (ref "D3") (pin "1") (pinfunction "A_1") (pintype "passive"))
      (node (ref "R1") (pin "1") (pinfunction "1_1") (pintype "passive"))
      (node (ref "U1") (pin "7") (pinfunction "REGIN_7") (pintype "passive"))
      (node (ref "U1") (pin "8") (pinfunction "VBUS_8") (pintype "passive"))
      (node (ref "USB1") (pin "A4") (pinfunction "VBUS_A4") (pintype "passive"))
      (node (ref "USB1") (pin "A9") (pinfunction "VBUS_A9") (pintype "passive"))
      (node (ref "USB1") (pin "B4") (pinfunction "VBUS_B4") (pintype "passive"))
      (node (ref "USB1") (pin "B9") (pinfunction "VBUS_B9") (pintype "passive"))
    )
    (net (code "79") (name "unconnected-(1-NC(VBREF)-Pad7)") (class "Default")
      (node (ref "1") (pin "7") (pinfunction "NC(VBREF)_7") (pintype "passive"))
    )
    (net (code "80") (name "unconnected-(U1-*SUSPEND-Pad11)") (class "Default")
      (node (ref "U1") (pin "11") (pinfunction "*SUSPEND_11") (pintype "passive"))
    )
    (net (code "81") (name "unconnected-(U1-CTS-Pad23)") (class "Default")
      (node (ref "U1") (pin "23") (pinfunction "CTS_23") (pintype "passive"))
    )
    (net (code "82") (name "unconnected-(U1-DCD-Pad1)") (class "Default")
      (node (ref "U1") (pin "1") (pinfunction "DCD_1") (pintype "passive"))
    )
    (net (code "83") (name "unconnected-(U1-DSR-Pad27)") (class "Default")
      (node (ref "U1") (pin "27") (pinfunction "DSR_27") (pintype "passive"))
    )
    (net (code "84") (name "unconnected-(U1-NC-Pad10)") (class "Default")
      (node (ref "U1") (pin "10") (pinfunction "NC_10") (pintype "passive"))
    )
    (net (code "85") (name "unconnected-(U1-NC-Pad13)") (class "Default")
      (node (ref "U1") (pin "13") (pinfunction "NC_13") (pintype "passive"))
    )
    (net (code "86") (name "unconnected-(U1-NC-Pad14)") (class "Default")
      (node (ref "U1") (pin "14") (pinfunction "NC_14") (pintype "passive"))
    )
    (net (code "87") (name "unconnected-(U1-NC-Pad15)") (class "Default")
      (node (ref "U1") (pin "15") (pinfunction "NC_15") (pintype "passive"))
    )
    (net (code "88") (name "unconnected-(U1-NC-Pad16)") (class "Default")
      (node (ref "U1") (pin "16") (pinfunction "NC_16") (pintype "passive"))
    )
    (net (code "89") (name "unconnected-(U1-NC-Pad17)") (class "Default")
      (node (ref "U1") (pin "17") (pinfunction "NC_17") (pintype "passive"))
    )
    (net (code "90") (name "unconnected-(U1-NC-Pad18)") (class "Default")
      (node (ref "U1") (pin "18") (pinfunction "NC_18") (pintype "passive"))
    )
    (net (code "91") (name "unconnected-(U1-NC-Pad19)") (class "Default")
      (node (ref "U1") (pin "19") (pinfunction "NC_19") (pintype "passive"))
    )
    (net (code "92") (name "unconnected-(U1-NC-Pad20)") (class "Default")
      (node (ref "U1") (pin "20") (pinfunction "NC_20") (pintype "passive"))
    )
    (net (code "93") (name "unconnected-(U1-NC-Pad21)") (class "Default")
      (node (ref "U1") (pin "21") (pinfunction "NC_21") (pintype "passive"))
    )
    (net (code "94") (name "unconnected-(U1-NC-Pad22)") (class "Default")
      (node (ref "U1") (pin "22") (pinfunction "NC_22") (pintype "passive"))
    )
    (net (code "95") (name "unconnected-(U1-RI-Pad2)") (class "Default")
      (node (ref "U1") (pin "2") (pinfunction "RI_2") (pintype "passive"))
    )
    (net (code "96") (name "unconnected-(U1-SUSPEND-Pad12)") (class "Default")
      (node (ref "U1") (pin "12") (pinfunction "SUSPEND_12") (pintype "passive"))
    )
    (net (code "97") (name "unconnected-(U1-VDD-Pad6)") (class "Default")
      (node (ref "U1") (pin "6") (pinfunction "VDD_6") (pintype "passive"))
    )
    (net (code "98") (name "unconnected-(U4-CAP1_NC-Pad48)") (class "Default")
      (node (ref "U4") (pin "48") (pinfunction "CAP1_NC_48") (pintype "passive"))
    )
    (net (code "99") (name "unconnected-(U4-CAP2_NC-Pad47)") (class "Default")
      (node (ref "U4") (pin "47") (pinfunction "CAP2_NC_47") (pintype "passive"))
    )
    (net (code "100") (name "unconnected-(U4-VDD_SDIO_NC-Pad26)") (class "Default")
      (node (ref "U4") (pin "26") (pinfunction "VDD_SDIO_NC_26") (pintype "passive"))
    )
    (net (code "101") (name "unconnected-(U4-XTAL_N_NC-Pad44)") (class "Default")
      (node (ref "U4") (pin "44") (pinfunction "XTAL_N_NC_44") (pintype "passive"))
    )
    (net (code "102") (name "unconnected-(U4-XTAL_P_NC-Pad45)") (class "Default")
      (node (ref "U4") (pin "45") (pinfunction "XTAL_P_NC_45") (pintype "passive"))
    )
    (net (code "103") (name "unconnected-(U5-NC-Pad8)") (class "Default")
      (node (ref "U5") (pin "8") (pinfunction "NC_8") (pintype "passive+no_connect"))
    )
    (net (code "104") (name "unconnected-(USB1-RX1+-PadB11)") (class "Default")
      (node (ref "USB1") (pin "B11") (pinfunction "RX1+_B11") (pintype "passive"))
    )
    (net (code "105") (name "unconnected-(USB1-RX1--PadB10)") (class "Default")
      (node (ref "USB1") (pin "B10") (pinfunction "RX1-_B10") (pintype "passive"))
    )
    (net (code "106") (name "unconnected-(USB1-RX2+-PadA11)") (class "Default")
      (node (ref "USB1") (pin "A11") (pinfunction "RX2+_A11") (pintype "passive"))
    )
    (net (code "107") (name "unconnected-(USB1-RX2--PadA10)") (class "Default")
      (node (ref "USB1") (pin "A10") (pinfunction "RX2-_A10") (pintype "passive"))
    )
    (net (code "108") (name "unconnected-(USB1-SBU1-PadA8)") (class "Default")
      (node (ref "USB1") (pin "A8") (pinfunction "SBU1_A8") (pintype "passive"))
    )
    (net (code "109") (name "unconnected-(USB1-SBU2-PadB8)") (class "Default")
      (node (ref "USB1") (pin "B8") (pinfunction "SBU2_B8") (pintype "passive"))
    )
    (net (code "110") (name "unconnected-(USB1-TX1+-PadA2)") (class "Default")
      (node (ref "USB1") (pin "A2") (pinfunction "TX1+_A2") (pintype "passive"))
    )
    (net (code "111") (name "unconnected-(USB1-TX1--PadA3)") (class "Default")
      (node (ref "USB1") (pin "A3") (pinfunction "TX1-_A3") (pintype "passive"))
    )
    (net (code "112") (name "unconnected-(USB1-TX2+-PadB2)") (class "Default")
      (node (ref "USB1") (pin "B2") (pinfunction "TX2+_B2") (pintype "passive"))
    )
    (net (code "113") (name "unconnected-(USB1-TX2--PadB3)") (class "Default")
      (node (ref "USB1") (pin "B3") (pinfunction "TX2-_B3") (pintype "passive"))
    )
  )
)
